# COEXPIX_schematics.net
KiCad netlist of a schematic drawn in Altium Designer
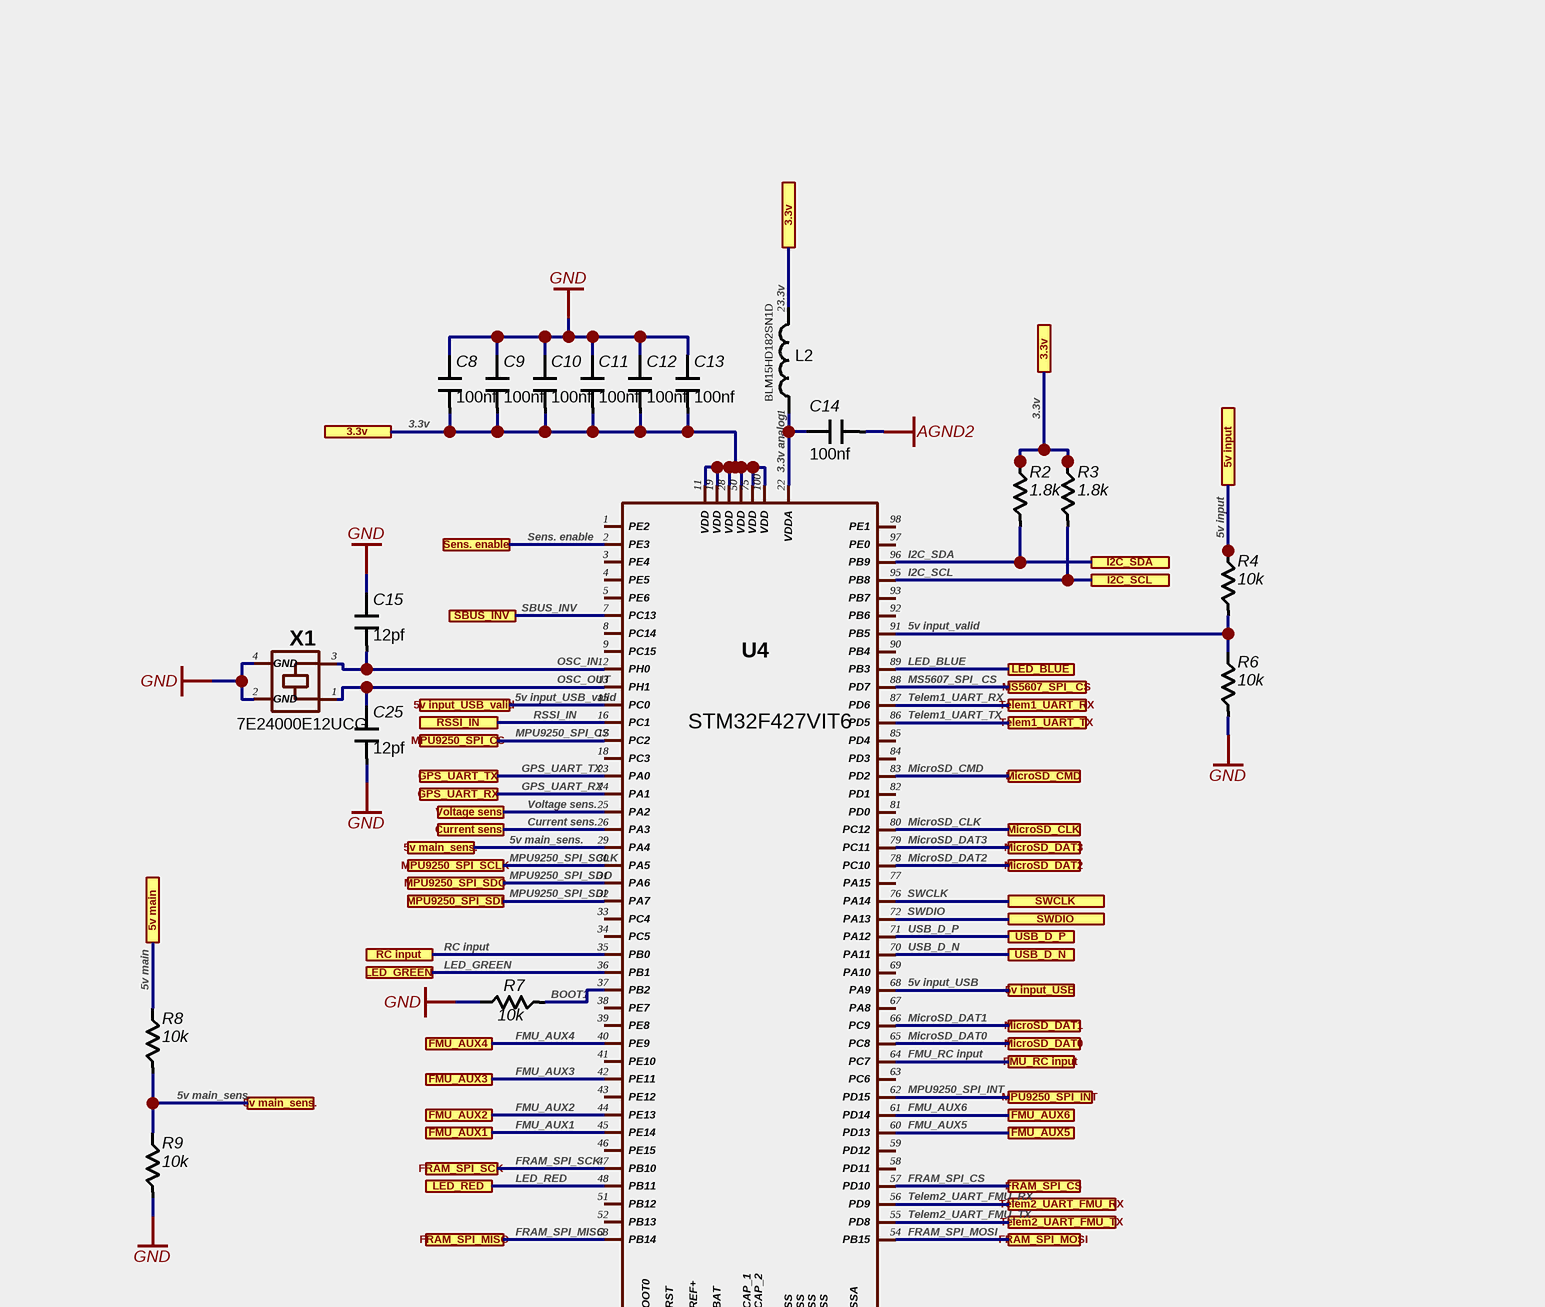
[diagram p0: COEXPIX schematics.SchDoc, top left]
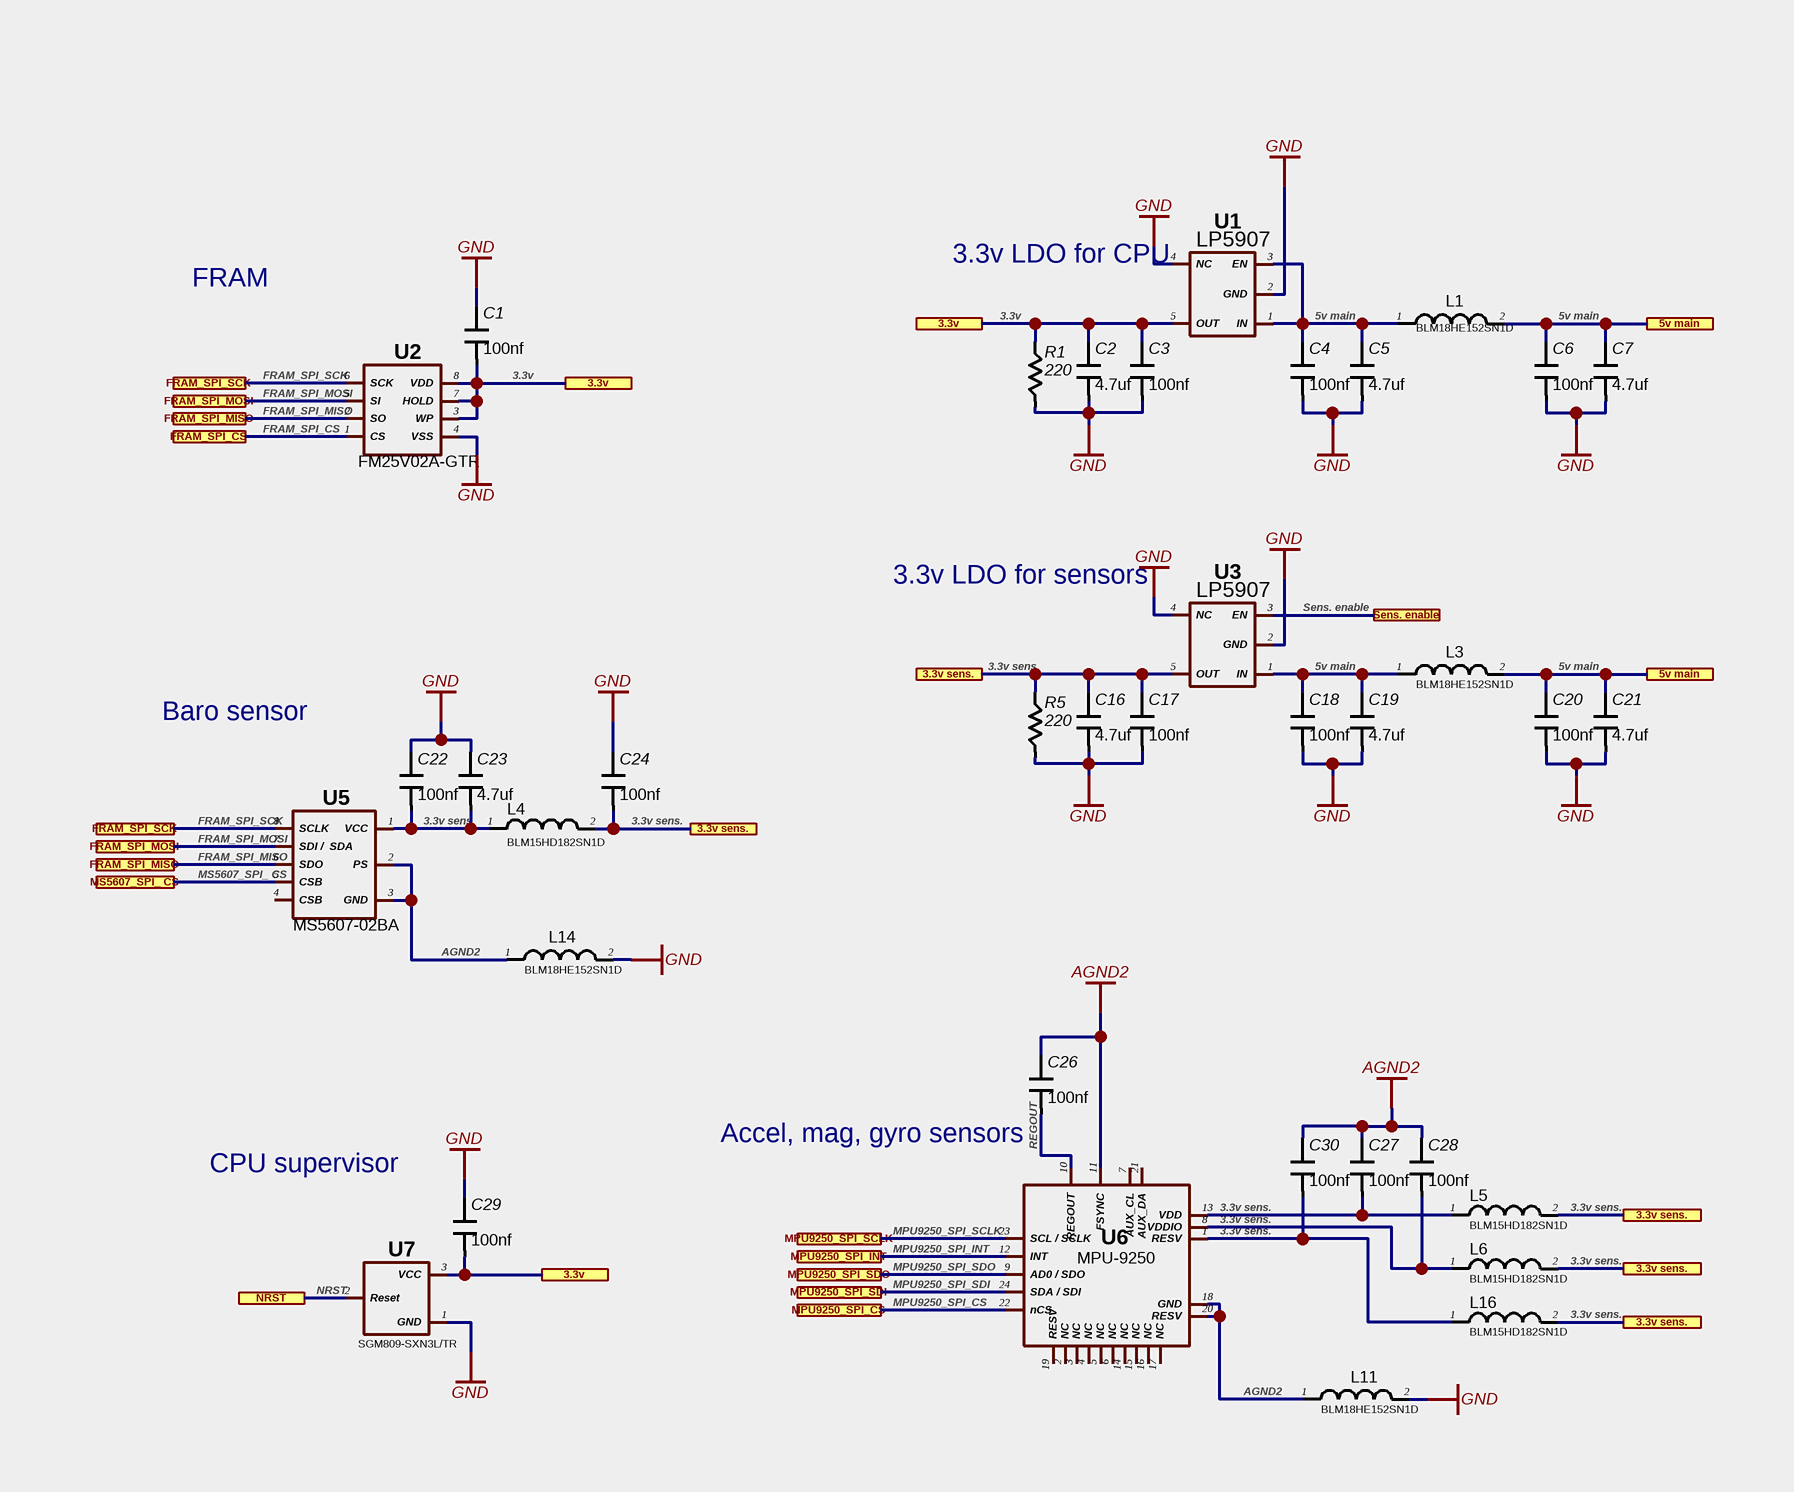
[diagram p1: COEXPIX schematics.SchDoc, top right]
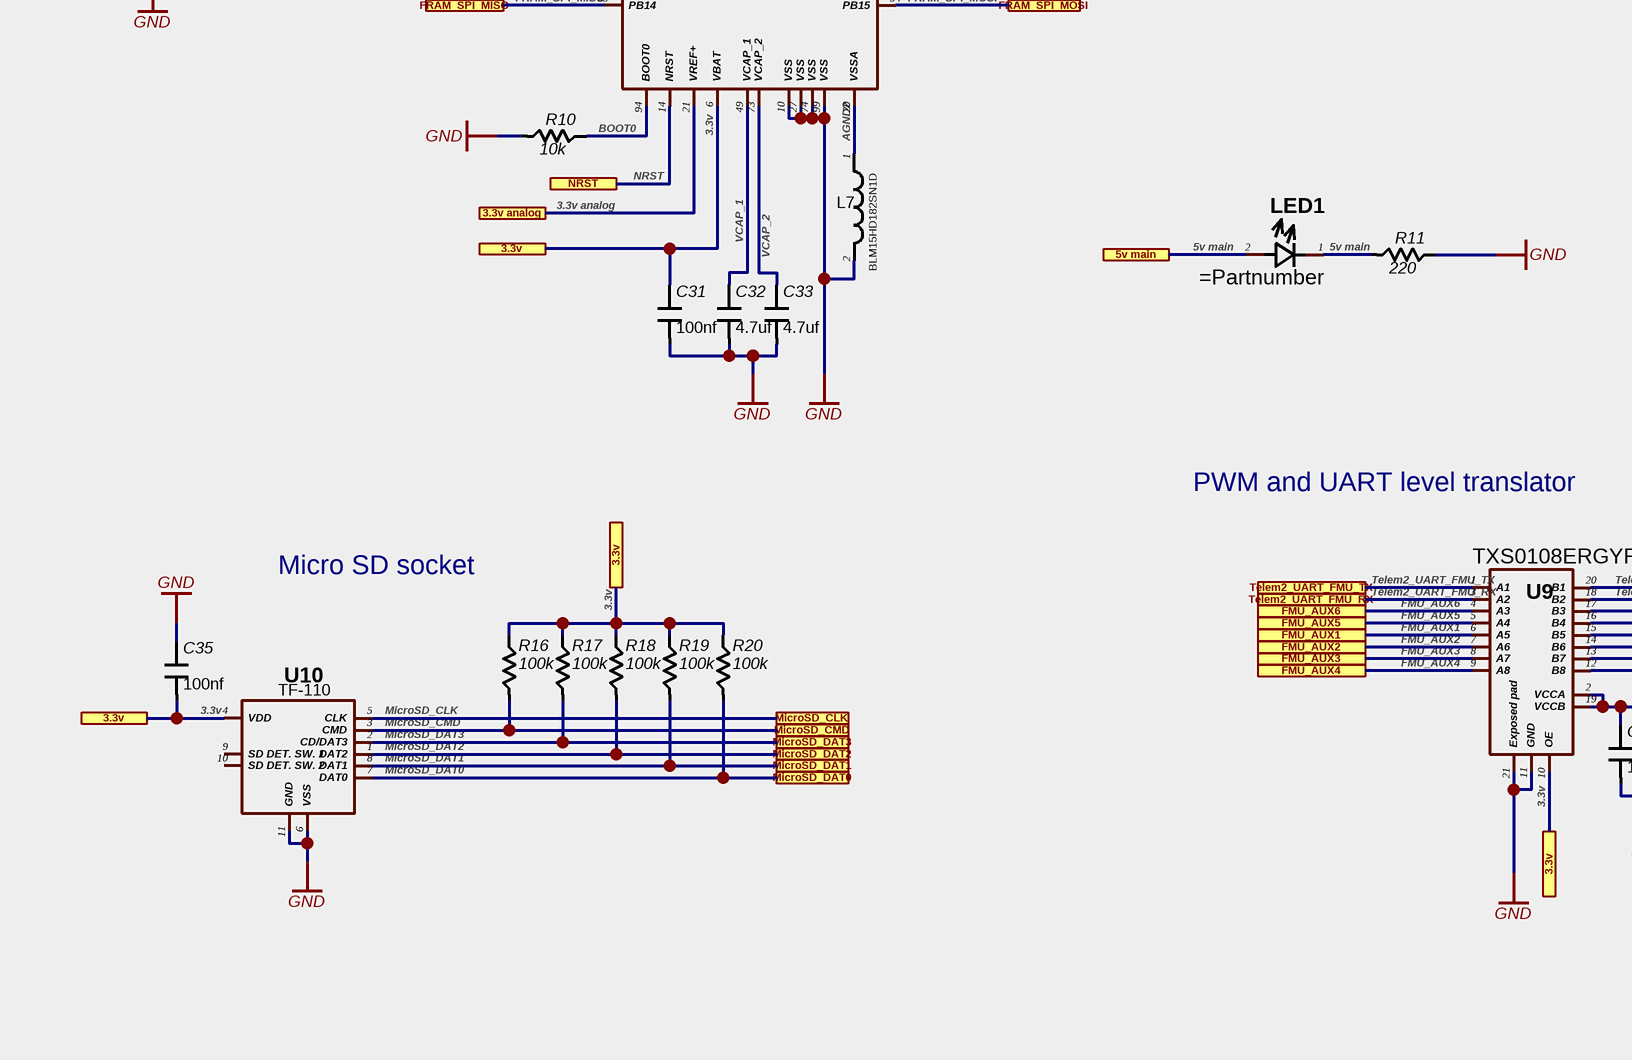
[diagram p2: COEXPIX schematics.SchDoc, bottom left]
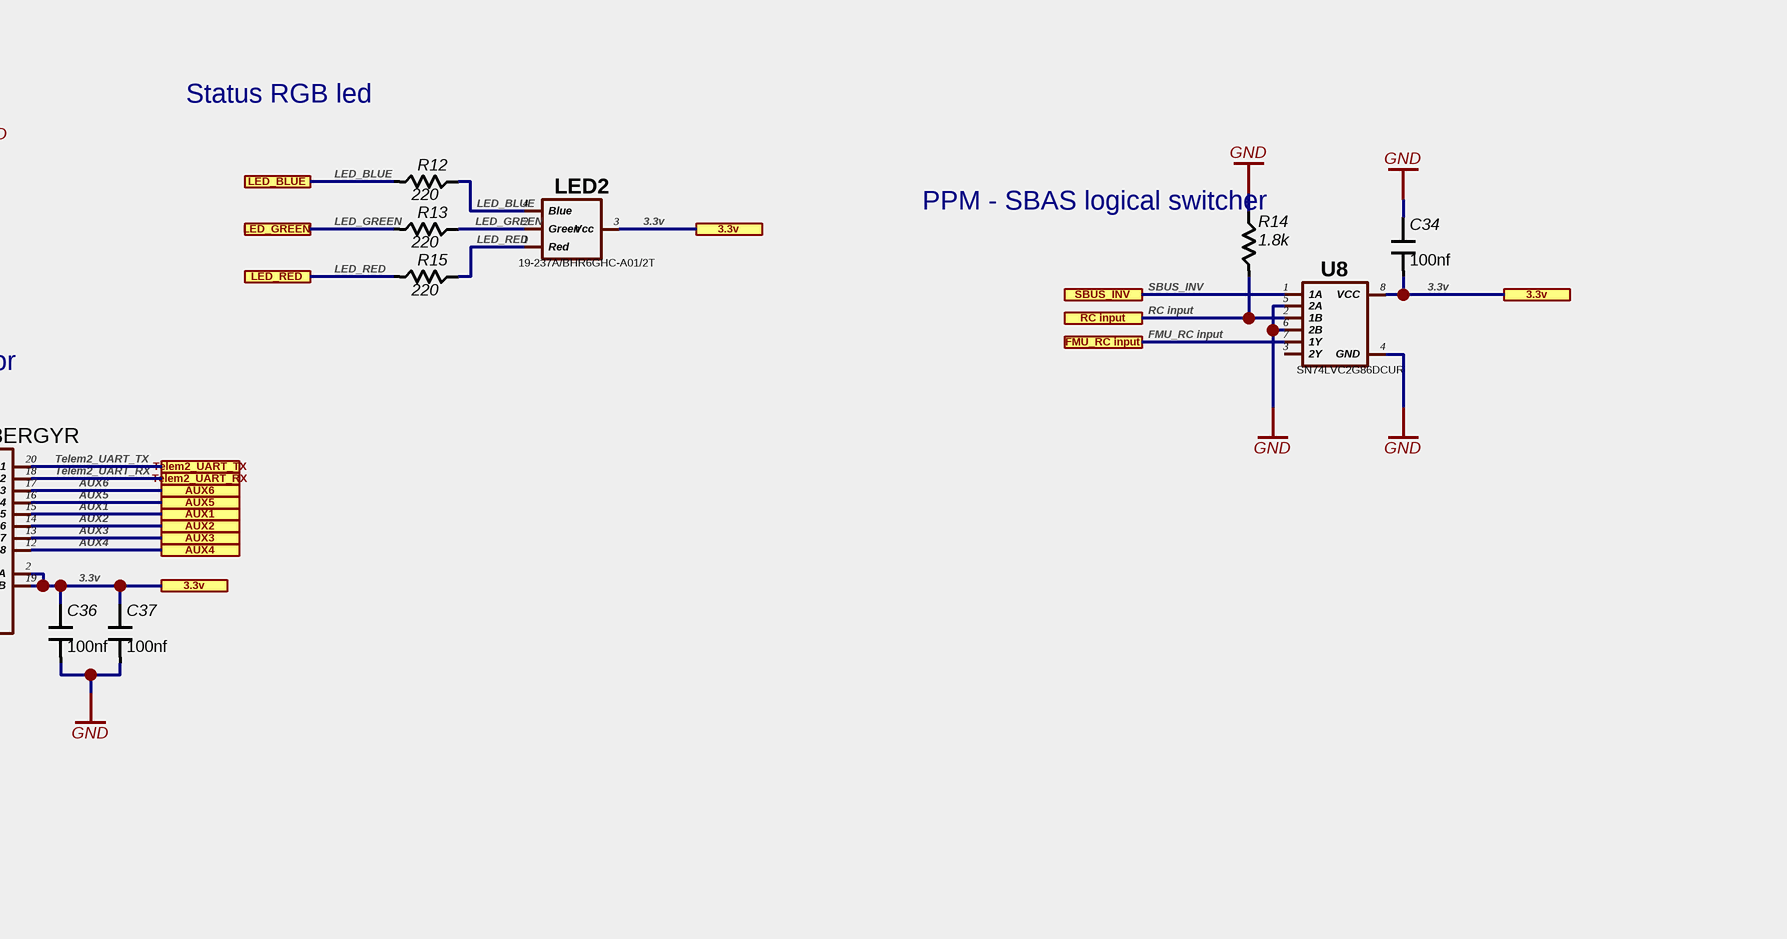
[diagram p3: COEXPIX schematics.SchDoc, bottom right]

(export (version "E")
  (design (tool "Eeschema 10.0.6"))
  (components
    (comp (ref "C1")
      (value "100nf")
      (footprint "Capasitor 0402")
      (description "Multilayer Ceramic Capacitors MLCC - SMD/SMT 100nF 16V 0402")
      (fields (field (name "PART NUMBER") "CC0402KRX7R7BB104") (field (name "MANUFACTURER") "YAGEO"))
      (libsource (lib "Schematic symbols library") (part "Capacitor MLCC"))
    )
    (comp (ref "C2")
      (value "4.7uf")
      (footprint "Capasitor 0402")
      (description "4.7uF ±20% 6.3V X5R 0402 Multilayer Ceramic Capacitor")
      (fields (field (name "PART NUMBER") "JMK105BBJ475MV-F") (field (name "MANUFACTURER") "Taiyo Yuden"))
      (libsource (lib "Schematic symbols library") (part "Capacitor MLCC"))
    )
    (comp (ref "C3")
      (value "100nf")
      (footprint "Capasitor 0402")
      (description "Multilayer Ceramic Capacitors MLCC - SMD/SMT 100nF 16V 0402")
      (fields (field (name "PART NUMBER") "CC0402KRX7R7BB104") (field (name "MANUFACTURER") "YAGEO"))
      (libsource (lib "Schematic symbols library") (part "Capacitor MLCC"))
    )
    (comp (ref "C4")
      (value "100nf")
      (footprint "Capasitor 0402")
      (description "Multilayer Ceramic Capacitors MLCC - SMD/SMT 100nF 16V 0402")
      (fields (field (name "PART NUMBER") "CC0402KRX7R7BB104") (field (name "MANUFACTURER") "YAGEO"))
      (libsource (lib "Schematic symbols library") (part "Capacitor MLCC"))
    )
    (comp (ref "C5")
      (value "4.7uf")
      (footprint "Capasitor 0402")
      (description "4.7uF ±20% 6.3V X5R 0402 Multilayer Ceramic Capacitor")
      (fields (field (name "PART NUMBER") "JMK105BBJ475MV-F") (field (name "MANUFACTURER") "Taiyo Yuden"))
      (libsource (lib "") (part "Capacitor MLCC_1"))
    )
    (comp (ref "C6")
      (value "100nf")
      (footprint "Capasitor 0402")
      (description "Multilayer Ceramic Capacitors MLCC - SMD/SMT 100nF 16V 0402")
      (fields (field (name "PART NUMBER") "CC0402KRX7R7BB104") (field (name "MANUFACTURER") "YAGEO"))
      (libsource (lib "Schematic symbols library") (part "Capacitor MLCC"))
    )
    (comp (ref "C7")
      (value "4.7uf")
      (footprint "Capasitor 0402")
      (description "4.7uF ±20% 6.3V X5R 0402 Multilayer Ceramic Capacitor")
      (fields (field (name "PART NUMBER") "JMK105BBJ475MV-F") (field (name "MANUFACTURER") "Taiyo Yuden"))
      (libsource (lib "Schematic symbols library") (part "Capacitor MLCC"))
    )
    (comp (ref "C8")
      (value "100nf")
      (footprint "Capasitor 0402")
      (description "Multilayer Ceramic Capacitors MLCC - SMD/SMT 100nF 16V 0402")
      (fields (field (name "PART NUMBER") "CC0402KRX7R7BB104") (field (name "MANUFACTURER") "YAGEO"))
      (libsource (lib "Schematic symbols library") (part "Capacitor MLCC"))
    )
    (comp (ref "C9")
      (value "100nf")
      (footprint "Capasitor 0402")
      (description "Multilayer Ceramic Capacitors MLCC - SMD/SMT 100nF 16V 0402")
      (fields (field (name "PART NUMBER") "CC0402KRX7R7BB104") (field (name "MANUFACTURER") "YAGEO"))
      (libsource (lib "Schematic symbols library") (part "Capacitor MLCC"))
    )
    (comp (ref "C10")
      (value "100nf")
      (footprint "Capasitor 0402")
      (description "Multilayer Ceramic Capacitors MLCC - SMD/SMT 100nF 16V 0402")
      (fields (field (name "PART NUMBER") "CC0402KRX7R7BB104") (field (name "MANUFACTURER") "YAGEO"))
      (libsource (lib "Schematic symbols library") (part "Capacitor MLCC"))
    )
    (comp (ref "C11")
      (value "100nf")
      (footprint "Capasitor 0402")
      (description "Multilayer Ceramic Capacitors MLCC - SMD/SMT 100nF 16V 0402")
      (fields (field (name "PART NUMBER") "CC0402KRX7R7BB104") (field (name "MANUFACTURER") "YAGEO"))
      (libsource (lib "Schematic symbols library") (part "Capacitor MLCC"))
    )
    (comp (ref "C12")
      (value "100nf")
      (footprint "Capasitor 0402")
      (description "Multilayer Ceramic Capacitors MLCC - SMD/SMT 100nF 16V 0402")
      (fields (field (name "PART NUMBER") "CC0402KRX7R7BB104") (field (name "MANUFACTURER") "YAGEO"))
      (libsource (lib "Schematic symbols library") (part "Capacitor MLCC"))
    )
    (comp (ref "C13")
      (value "100nf")
      (footprint "Capasitor 0402")
      (description "Multilayer Ceramic Capacitors MLCC - SMD/SMT 100nF 16V 0402")
      (fields (field (name "PART NUMBER") "CC0402KRX7R7BB104") (field (name "MANUFACTURER") "YAGEO"))
      (libsource (lib "Schematic symbols library") (part "Capacitor MLCC"))
    )
    (comp (ref "C14")
      (value "100nf")
      (footprint "Capasitor 0402")
      (description "Multilayer Ceramic Capacitors MLCC - SMD/SMT 100nF 16V 0402")
      (fields (field (name "PART NUMBER") "CC0402KRX7R7BB104") (field (name "MANUFACTURER") "YAGEO"))
      (libsource (lib "Schematic symbols library") (part "Capacitor MLCC"))
    )
    (comp (ref "C15")
      (value "12pf")
      (footprint "Capasitor 0402")
      (description "Multilayer Ceramic Capacitors MLCC - SMD/SMT 12pF 50V 0402")
      (fields (field (name "PART NUMBER") "CC0402JRNPO9BN120") (field (name "MANUFACTURER") "YAGEO"))
      (libsource (lib "Schematic symbols library") (part "Capacitor MLCC"))
    )
    (comp (ref "C16")
      (value "4.7uf")
      (footprint "Capasitor 0402")
      (description "4.7uF ±20% 6.3V X5R 0402 Multilayer Ceramic Capacitor")
      (fields (field (name "PART NUMBER") "JMK105BBJ475MV-F") (field (name "MANUFACTURER") "Taiyo Yuden"))
      (libsource (lib "Schematic symbols library") (part "Capacitor MLCC"))
    )
    (comp (ref "C17")
      (value "100nf")
      (footprint "Capasitor 0402")
      (description "Multilayer Ceramic Capacitors MLCC - SMD/SMT 100nF 16V 0402")
      (fields (field (name "PART NUMBER") "CC0402KRX7R7BB104") (field (name "MANUFACTURER") "YAGEO"))
      (libsource (lib "Schematic symbols library") (part "Capacitor MLCC"))
    )
    (comp (ref "C18")
      (value "100nf")
      (footprint "Capasitor 0402")
      (description "Multilayer Ceramic Capacitors MLCC - SMD/SMT 100nF 16V 0402")
      (fields (field (name "PART NUMBER") "CC0402KRX7R7BB104") (field (name "MANUFACTURER") "YAGEO"))
      (libsource (lib "Schematic symbols library") (part "Capacitor MLCC"))
    )
    (comp (ref "C19")
      (value "4.7uf")
      (footprint "Capasitor 0402")
      (description "4.7uF ±20% 6.3V X5R 0402 Multilayer Ceramic Capacitor")
      (fields (field (name "PART NUMBER") "JMK105BBJ475MV-F") (field (name "MANUFACTURER") "Taiyo Yuden"))
      (libsource (lib "") (part "Capacitor MLCC_1"))
    )
    (comp (ref "C20")
      (value "100nf")
      (footprint "Capasitor 0402")
      (description "Multilayer Ceramic Capacitors MLCC - SMD/SMT 100nF 16V 0402")
      (fields (field (name "PART NUMBER") "CC0402KRX7R7BB104") (field (name "MANUFACTURER") "YAGEO"))
      (libsource (lib "Schematic symbols library") (part "Capacitor MLCC"))
    )
    (comp (ref "C21")
      (value "4.7uf")
      (footprint "Capasitor 0402")
      (description "4.7uF ±20% 6.3V X5R 0402 Multilayer Ceramic Capacitor")
      (fields (field (name "PART NUMBER") "JMK105BBJ475MV-F") (field (name "MANUFACTURER") "Taiyo Yuden"))
      (libsource (lib "Schematic symbols library") (part "Capacitor MLCC"))
    )
    (comp (ref "C22")
      (value "100nf")
      (footprint "Capasitor 0402")
      (description "Multilayer Ceramic Capacitors MLCC - SMD/SMT 100nF 16V 0402")
      (fields (field (name "PART NUMBER") "CC0402KRX7R7BB104") (field (name "MANUFACTURER") "YAGEO"))
      (libsource (lib "Schematic symbols library") (part "Capacitor MLCC"))
    )
    (comp (ref "C23")
      (value "4.7uf")
      (footprint "Capasitor 0402")
      (description "4.7uF ±20% 6.3V X5R 0402 Multilayer Ceramic Capacitor")
      (fields (field (name "PART NUMBER") "JMK105BBJ475MV-F") (field (name "MANUFACTURER") "Taiyo Yuden"))
      (libsource (lib "Schematic symbols library") (part "Capacitor MLCC"))
    )
    (comp (ref "C24")
      (value "100nf")
      (footprint "Capasitor 0402")
      (description "Multilayer Ceramic Capacitors MLCC - SMD/SMT 100nF 16V 0402")
      (fields (field (name "PART NUMBER") "CC0402KRX7R7BB104") (field (name "MANUFACTURER") "YAGEO"))
      (libsource (lib "Schematic symbols library") (part "Capacitor MLCC"))
    )
    (comp (ref "C25")
      (value "12pf")
      (footprint "Capasitor 0402")
      (description "Multilayer Ceramic Capacitors MLCC - SMD/SMT 12pF 50V 0402")
      (fields (field (name "PART NUMBER") "CC0402JRNPO9BN120") (field (name "MANUFACTURER") "YAGEO"))
      (libsource (lib "Schematic symbols library") (part "Capacitor MLCC"))
    )
    (comp (ref "C26")
      (value "100nf")
      (footprint "Capasitor 0402")
      (description "Multilayer Ceramic Capacitors MLCC - SMD/SMT 100nF 16V 0402")
      (fields (field (name "PART NUMBER") "CC0402KRX7R7BB104") (field (name "MANUFACTURER") "YAGEO"))
      (libsource (lib "Schematic symbols library") (part "Capacitor MLCC"))
    )
    (comp (ref "C27")
      (value "100nf")
      (footprint "Capasitor 0402")
      (description "Multilayer Ceramic Capacitors MLCC - SMD/SMT 100nF 16V 0402")
      (fields (field (name "PART NUMBER") "CC0402KRX7R7BB104") (field (name "MANUFACTURER") "YAGEO"))
      (libsource (lib "") (part "Capacitor MLCC_1"))
    )
    (comp (ref "C28")
      (value "100nf")
      (footprint "Capasitor 0402")
      (description "Multilayer Ceramic Capacitors MLCC - SMD/SMT 100nF 16V 0402")
      (fields (field (name "PART NUMBER") "CC0402KRX7R7BB104") (field (name "MANUFACTURER") "YAGEO"))
      (libsource (lib "Schematic symbols library") (part "Capacitor MLCC"))
    )
    (comp (ref "C29")
      (value "100nf")
      (footprint "Capasitor 0402")
      (description "Multilayer Ceramic Capacitors MLCC - SMD/SMT 100nF 16V 0402")
      (fields (field (name "PART NUMBER") "CC0402KRX7R7BB104") (field (name "MANUFACTURER") "YAGEO"))
      (libsource (lib "Schematic symbols library") (part "Capacitor MLCC"))
    )
    (comp (ref "C30")
      (value "100nf")
      (footprint "Capasitor 0402")
      (description "Multilayer Ceramic Capacitors MLCC - SMD/SMT 100nF 16V 0402")
      (fields (field (name "PART NUMBER") "CC0402KRX7R7BB104") (field (name "MANUFACTURER") "YAGEO"))
      (libsource (lib "Schematic symbols library") (part "Capacitor MLCC"))
    )
    (comp (ref "C31")
      (value "100nf")
      (footprint "Capasitor 0402")
      (description "Multilayer Ceramic Capacitors MLCC - SMD/SMT 100nF 16V 0402")
      (fields (field (name "PART NUMBER") "CC0402KRX7R7BB104") (field (name "MANUFACTURER") "YAGEO"))
      (libsource (lib "Schematic symbols library") (part "Capacitor MLCC"))
    )
    (comp (ref "C32")
      (value "4.7uf")
      (footprint "Capasitor 0402")
      (description "4.7uF ±20% 6.3V X5R 0402 Multilayer Ceramic Capacitor")
      (fields (field (name "PART NUMBER") "JMK105BBJ475MV-F") (field (name "MANUFACTURER") "Taiyo Yuden"))
      (libsource (lib "Schematic symbols library") (part "Capacitor MLCC"))
    )
    (comp (ref "C33")
      (value "4.7uf")
      (footprint "Capasitor 0402")
      (description "4.7uF ±20% 6.3V X5R 0402 Multilayer Ceramic Capacitor")
      (fields (field (name "PART NUMBER") "JMK105BBJ475MV-F") (field (name "MANUFACTURER") "Taiyo Yuden"))
      (libsource (lib "Schematic symbols library") (part "Capacitor MLCC"))
    )
    (comp (ref "C34")
      (value "100nf")
      (footprint "Capasitor 0402")
      (description "Multilayer Ceramic Capacitors MLCC - SMD/SMT 100nF 16V 0402")
      (fields (field (name "PART NUMBER") "CC0402KRX7R7BB104") (field (name "MANUFACTURER") "YAGEO"))
      (libsource (lib "Schematic symbols library") (part "Capacitor MLCC"))
    )
    (comp (ref "C35")
      (value "100nf")
      (footprint "Capasitor 0402")
      (description "Multilayer Ceramic Capacitors MLCC - SMD/SMT 100nF 16V 0402")
      (fields (field (name "PART NUMBER") "CC0402KRX7R7BB104") (field (name "MANUFACTURER") "YAGEO"))
      (libsource (lib "Schematic symbols library") (part "Capacitor MLCC"))
    )
    (comp (ref "C36")
      (value "100nf")
      (footprint "Capasitor 0402")
      (description "Multilayer Ceramic Capacitors MLCC - SMD/SMT 100nF 16V 0402")
      (fields (field (name "PART NUMBER") "CC0402KRX7R7BB104") (field (name "MANUFACTURER") "YAGEO"))
      (libsource (lib "Schematic symbols library") (part "Capacitor MLCC"))
    )
    (comp (ref "C37")
      (value "100nf")
      (footprint "Capasitor 0402")
      (description "Multilayer Ceramic Capacitors MLCC - SMD/SMT 100nF 16V 0402")
      (fields (field (name "PART NUMBER") "CC0402KRX7R7BB104") (field (name "MANUFACTURER") "YAGEO"))
      (libsource (lib "Schematic symbols library") (part "Capacitor MLCC"))
    )
    (comp (ref "L1")
      (value "BLM18HE152SN1D")
      (footprint "Ferrite bead 0603")
      (description "Beads 0603")
      (fields (field (name "MANUFACTURER") "Murata"))
      (libsource (lib "Schematic symbols library") (part "FB / Inductor"))
    )
    (comp (ref "L2")
      (value "BLM15HD182SN1D")
      (footprint "Ferrite bead 0402")
      (description "1.8kΩ @ 100MHz 200mA 1 2.2Ω 0402 Ferrite Bead")
      (fields (field (name "MANUFACTURER") "Murata Electronics"))
      (libsource (lib "Schematic symbols library") (part "FB / Inductor"))
    )
    (comp (ref "L3")
      (value "BLM18HE152SN1D")
      (footprint "Ferrite bead 0603")
      (description "Beads 0603")
      (fields (field (name "MANUFACTURER") "Murata"))
      (libsource (lib "Schematic symbols library") (part "FB / Inductor"))
    )
    (comp (ref "L4")
      (value "BLM15HD182SN1D")
      (footprint "Ferrite bead 0402")
      (description "1.8kΩ @ 100MHz 200mA 1 2.2Ω 0402 Ferrite Bead")
      (fields (field (name "MANUFACTURER") "Murata Electronics"))
      (libsource (lib "Schematic symbols library") (part "FB / Inductor"))
    )
    (comp (ref "L5")
      (value "BLM15HD182SN1D")
      (footprint "Ferrite bead 0402")
      (description "1.8kΩ @ 100MHz 200mA 1 2.2Ω 0402 Ferrite Bead")
      (fields (field (name "MANUFACTURER") "Murata Electronics"))
      (libsource (lib "Schematic symbols library") (part "FB / Inductor"))
    )
    (comp (ref "L6")
      (value "BLM15HD182SN1D")
      (footprint "Ferrite bead 0402")
      (description "1.8kΩ @ 100MHz 200mA 1 2.2Ω 0402 Ferrite Bead")
      (fields (field (name "MANUFACTURER") "Murata Electronics"))
      (libsource (lib "Schematic symbols library") (part "FB / Inductor"))
    )
    (comp (ref "L7")
      (value "BLM15HD182SN1D")
      (footprint "Ferrite bead 0402")
      (description "1.8kΩ @ 100MHz 200mA 1 2.2Ω 0402 Ferrite Bead")
      (fields (field (name "MANUFACTURER") "Murata Electronics"))
      (libsource (lib "Schematic symbols library") (part "FB / Inductor"))
    )
    (comp (ref "L11")
      (value "BLM18HE152SN1D")
      (footprint "Ferrite bead 0603")
      (description "Beads 0603")
      (fields (field (name "MANUFACTURER") "Murata"))
      (libsource (lib "Schematic symbols library") (part "FB / Inductor"))
    )
    (comp (ref "L14")
      (value "BLM18HE152SN1D")
      (footprint "Ferrite bead 0603")
      (description "Beads 0603")
      (fields (field (name "MANUFACTURER") "Murata"))
      (libsource (lib "Schematic symbols library") (part "FB / Inductor"))
    )
    (comp (ref "L16")
      (value "BLM15HD182SN1D")
      (footprint "Ferrite bead 0402")
      (description "1.8kΩ @ 100MHz 200mA 1 2.2Ω 0402 Ferrite Bead")
      (fields (field (name "MANUFACTURER") "Murata Electronics"))
      (libsource (lib "Schematic symbols library") (part "FB / Inductor"))
    )
    (comp (ref "LED1")
      (value "~")
      (footprint "Led 0603")
      (description "Green 520~535nm 0603 Light Emitting Diode")
      (fields
        (field (name "PART NUMBER") "19-217/GHC-YR1S2/3T")
        (field (name "MANUFACTURER") "Everlight Elec")
      )
      (libsource (lib "Schematic symbols library") (part "LED"))
    )
    (comp (ref "LED2")
      (value "19-237A/BHR6GHC-A01/2T")
      (footprint "Everlight RGB LED")
      (description "RGB614~628nmRed,518~528nmGreen,465~475nmBlue SMD,1.6x1.6mm Light Emitting Diode")
      (fields (field (name "MANUFACTURER") "Everlight Elec"))
      (libsource (lib "Schematic symbols library") (part "Everlight 19-237A"))
    )
    (comp (ref "R1")
      (value "220")
      (footprint "Resistor 0402")
      (description "Chip Resistor - Surface Mount 220Ohms ±1% 1/16W 0402")
      (fields (field (name "PART NUMBER") "0402WGF2200TCE") (field (name "MANUFACTURER") "Uniroyal Elec"))
      (libsource (lib "Schematic symbols library") (part "Resistor"))
    )
    (comp (ref "R2")
      (value "1.8k")
      (footprint "Resistor 0402")
      (description "Chip Resistor - Surface Mount 1.8KOhms ±1% 1/16W 0402")
      (fields (field (name "PART NUMBER") "0402WGF1801TCE") (field (name "MANUFACTURER") "Uniroyal Elec"))
      (libsource (lib "Schematic symbols library") (part "Resistor"))
    )
    (comp (ref "R3")
      (value "1.8k")
      (footprint "Resistor 0402")
      (description "Chip Resistor - Surface Mount 1.8KOhms ±1% 1/16W 0402")
      (fields (field (name "PART NUMBER") "0402WGF1801TCE") (field (name "MANUFACTURER") "Uniroyal Elec"))
      (libsource (lib "Schematic symbols library") (part "Resistor"))
    )
    (comp (ref "R4")
      (value "10k")
      (footprint "Resistor 0402")
      (description "Chip Resistor - Surface Mount 10KOhms ±1% 1/16W 0402")
      (fields (field (name "PART NUMBER") "RC0402FR-0710KL") (field (name "MANUFACTURER") "YAGEO"))
      (libsource (lib "Schematic symbols library") (part "Resistor"))
    )
    (comp (ref "R5")
      (value "220")
      (footprint "Resistor 0402")
      (description "Chip Resistor - Surface Mount 220Ohms ±1% 1/16W 0402")
      (fields (field (name "PART NUMBER") "0402WGF2200TCE") (field (name "MANUFACTURER") "Uniroyal Elec"))
      (libsource (lib "Schematic symbols library") (part "Resistor"))
    )
    (comp (ref "R6")
      (value "10k")
      (footprint "Resistor 0402")
      (description "Chip Resistor - Surface Mount 10KOhms ±1% 1/16W 0402")
      (fields (field (name "PART NUMBER") "RC0402FR-0710KL") (field (name "MANUFACTURER") "YAGEO"))
      (libsource (lib "Schematic symbols library") (part "Resistor"))
    )
    (comp (ref "R7")
      (value "10k")
      (footprint "Resistor 0402")
      (description "Chip Resistor - Surface Mount 10KOhms ±1% 1/16W 0402")
      (fields (field (name "PART NUMBER") "RC0402FR-0710KL") (field (name "MANUFACTURER") "YAGEO"))
      (libsource (lib "Schematic symbols library") (part "Resistor"))
    )
    (comp (ref "R8")
      (value "10k")
      (footprint "Resistor 0402")
      (description "Chip Resistor - Surface Mount 10KOhms ±1% 1/16W 0402")
      (fields (field (name "PART NUMBER") "RC0402FR-0710KL") (field (name "MANUFACTURER") "YAGEO"))
      (libsource (lib "Schematic symbols library") (part "Resistor"))
    )
    (comp (ref "R9")
      (value "10k")
      (footprint "Resistor 0402")
      (description "Chip Resistor - Surface Mount 10KOhms ±1% 1/16W 0402")
      (fields (field (name "PART NUMBER") "RC0402FR-0710KL") (field (name "MANUFACTURER") "YAGEO"))
      (libsource (lib "Schematic symbols library") (part "Resistor"))
    )
    (comp (ref "R10")
      (value "10k")
      (footprint "Resistor 0402")
      (description "Chip Resistor - Surface Mount 10KOhms ±1% 1/16W 0402")
      (fields (field (name "PART NUMBER") "RC0402FR-0710KL") (field (name "MANUFACTURER") "YAGEO"))
      (libsource (lib "Schematic symbols library") (part "Resistor"))
    )
    (comp (ref "R11")
      (value "220")
      (footprint "Resistor 0402")
      (description "Chip Resistor - Surface Mount 220Ohms ±1% 1/16W 0402")
      (fields (field (name "PART NUMBER") "0402WGF2200TCE") (field (name "MANUFACTURER") "Uniroyal Elec"))
      (libsource (lib "Schematic symbols library") (part "Resistor"))
    )
    (comp (ref "R12")
      (value "220")
      (footprint "Resistor 0402")
      (description "Chip Resistor - Surface Mount 220Ohms ±1% 1/16W 0402")
      (fields (field (name "PART NUMBER") "0402WGF2200TCE") (field (name "MANUFACTURER") "Uniroyal Elec"))
      (libsource (lib "Schematic symbols library") (part "Resistor"))
    )
    (comp (ref "R13")
      (value "220")
      (footprint "Resistor 0402")
      (description "Chip Resistor - Surface Mount 220Ohms ±1% 1/16W 0402")
      (fields (field (name "PART NUMBER") "0402WGF2200TCE") (field (name "MANUFACTURER") "Uniroyal Elec"))
      (libsource (lib "Schematic symbols library") (part "Resistor"))
    )
    (comp (ref "R14")
      (value "1.8k")
      (footprint "Resistor 0402")
      (description "Chip Resistor - Surface Mount 1.8KOhms ±1% 1/16W 0402")
      (fields (field (name "PART NUMBER") "0402WGF1801TCE") (field (name "MANUFACTURER") "Uniroyal Elec"))
      (libsource (lib "Schematic symbols library") (part "Resistor"))
    )
    (comp (ref "R15")
      (value "220")
      (footprint "Resistor 0402")
      (description "Chip Resistor - Surface Mount 220Ohms ±1% 1/16W 0402")
      (fields (field (name "PART NUMBER") "0402WGF2200TCE") (field (name "MANUFACTURER") "Uniroyal Elec"))
      (libsource (lib "Schematic symbols library") (part "Resistor"))
    )
    (comp (ref "R16")
      (value "100k")
      (footprint "Resistor 0402")
      (description "Chip Resistor - Surface Mount 100KOhms ±1% 1/16W 0402")
      (fields (field (name "PART NUMBER") "RC0402FR-07100KL") (field (name "MANUFACTURER") "YAGEO"))
      (libsource (lib "Schematic symbols library") (part "Resistor"))
    )
    (comp (ref "R17")
      (value "100k")
      (footprint "Resistor 0402")
      (description "Chip Resistor - Surface Mount 100KOhms ±1% 1/16W 0402")
      (fields (field (name "PART NUMBER") "RC0402FR-07100KL") (field (name "MANUFACTURER") "YAGEO"))
      (libsource (lib "Schematic symbols library") (part "Resistor"))
    )
    (comp (ref "R18")
      (value "100k")
      (footprint "Resistor 0402")
      (description "Chip Resistor - Surface Mount 100KOhms ±1% 1/16W 0402")
      (fields (field (name "PART NUMBER") "RC0402FR-07100KL") (field (name "MANUFACTURER") "YAGEO"))
      (libsource (lib "Schematic symbols library") (part "Resistor"))
    )
    (comp (ref "R19")
      (value "100k")
      (footprint "Resistor 0402")
      (description "Chip Resistor - Surface Mount 100KOhms ±1% 1/16W 0402")
      (fields (field (name "PART NUMBER") "RC0402FR-07100KL") (field (name "MANUFACTURER") "YAGEO"))
      (libsource (lib "Schematic symbols library") (part "Resistor"))
    )
    (comp (ref "R20")
      (value "100k")
      (footprint "Resistor 0402")
      (description "Chip Resistor - Surface Mount 100KOhms ±1% 1/16W 0402")
      (fields (field (name "PART NUMBER") "RC0402FR-07100KL") (field (name "MANUFACTURER") "YAGEO"))
      (libsource (lib "Schematic symbols library") (part "Resistor"))
    )
    (comp (ref "U1")
      (value "LP5907")
      (footprint "SOT23-5")
      (description "Linear Voltage Regulators SOT-23-5")
      (fields (field (name "MANUFACTURER") "Texas Instruments"))
      (libsource (lib "Schematic symbols library") (part "LP5907"))
    )
    (comp (ref "U2")
      (value "FM25V02A-GTR")
      (footprint "SOIC-8")
      (description "FRAM FRAM 256Kb (32K x 8) SPI SOIC-8_150mil")
      (fields (field (name "MANUFACTURER") "Cypress Semicon"))
      (libsource (lib "Schematic symbols library") (part "FM25V02A"))
    )
    (comp (ref "U3")
      (value "LP5907")
      (footprint "SOT23-5")
      (description "Linear Voltage Regulators SOT-23-5")
      (fields (field (name "MANUFACTURER") "Texas Instruments"))
      (libsource (lib "Schematic symbols library") (part "LP5907"))
    )
    (comp (ref "U4")
      (value "STM32F427VIT6")
      (footprint "LQFP100 0.5")
      (description "ARM® Cortex®-M4 STM32F4 Microcontroller IC 32-Bit 180MHz 2MB (2M x 8) FLASH 100-LQFP (14x14)")
      (fields (field (name "MANUFACTURER") "STMicroelectronics"))
      (libsource (lib "Schematic symbols library") (part "STM32F427VIT6"))
    )
    (comp (ref "U5")
      (value "MS5607-02BA")
      (footprint "MS5611")
      (fields (field (name "MANUFACTURER") "meas-spec"))
      (libsource (lib "Schematic symbols library") (part "MS5607-02BA"))
    )
    (comp (ref "U6")
      (value "MPU-9250")
      (footprint "QFN24 3x3mm (0.4mm)")
      (description "IMU ACCEL/GYRO/MAG I2C/SPI 24QFN")
      (fields (field (name "MANUFACTURER") "TDK InvenSense"))
      (libsource (lib "Schematic symbols library") (part "mpu9250"))
    )
    (comp (ref "U7")
      (value "SGM809-SXN3L/TR")
      (footprint "SOT23-3 LP")
      (fields (field (name "MANUFACTURER") "SGMICRO"))
      (libsource (lib "Schematic symbols library") (part "SGM809-SXN3L/TR"))
    )
    (comp (ref "U8")
      (value "SN74LVC2G86DCUR")
      (footprint "VSSOP8 0.5mm")
      (description "74 Series SPST-NC 2 1.65V ~ 5.5V VSSOP-8_2x2.3x05P")
      (fields (field (name "MANUFACTURER") "Texas Instruments"))
      (libsource (lib "Schematic symbols library") (part "SN74LVC2G86DCUR"))
    )
    (comp (ref "U9")
      (value "TXS0108ERGYR")
      (footprint "VQFN20 4.50x3.50mm (0.5mm)")
      (description "Level Translators, Shifters VQFN-20")
      (fields (field (name "MANUFACTURER") "Texas Instruments"))
      (libsource (lib "Schematic symbols library") (part "TXS0108ERGYR"))
    )
    (comp (ref "U10")
      (value "TF-110")
      (footprint "MicroSD (2)")
      (description "microSD™ Memory Card 8 connector 11.25x11.35x1.32mm Card Sockets Connector")
      (fields (field (name "MANUFACTURER") "XUNPU"))
      (libsource (lib "Schematic symbols library") (part "MicroSD socket"))
    )
    (comp (ref "X1")
      (value "7E24000E12UCG")
      (footprint "SMD-2520_4P")
      (description "SMD Crystal Resonators 24MHz ±10ppm SMD-2520_4P")
      (fields (field (name "MANUFACTURER") "SHENZHEN CRYSTAL TECH"))
      (libsource (lib "Schematic symbols library") (part "Crystal oscillator"))
    )
  )
  (nets
    (net (code "1") (name "/3.3v") (class "Default")
      (node (ref "C1") (pin "2") (pinfunction "2_2") (pintype "passive"))
      (node (ref "C10") (pin "2") (pinfunction "2_2") (pintype "passive"))
      (node (ref "C11") (pin "2") (pinfunction "2_2") (pintype "passive"))
      (node (ref "C12") (pin "2") (pinfunction "2_2") (pintype "passive"))
      (node (ref "C13") (pin "2") (pinfunction "2_2") (pintype "passive"))
      (node (ref "C2") (pin "1") (pinfunction "1_1") (pintype "passive"))
      (node (ref "C29") (pin "2") (pinfunction "2_2") (pintype "passive"))
      (node (ref "C3") (pin "1") (pinfunction "1_1") (pintype "passive"))
      (node (ref "C31") (pin "1") (pinfunction "1_1") (pintype "passive"))
      (node (ref "C34") (pin "2") (pinfunction "2_2") (pintype "passive"))
      (node (ref "C35") (pin "2") (pinfunction "2_2") (pintype "passive"))
      (node (ref "C36") (pin "1") (pinfunction "1_1") (pintype "passive"))
      (node (ref "C37") (pin "1") (pinfunction "1_1") (pintype "passive"))
      (node (ref "C8") (pin "2") (pinfunction "2_2") (pintype "passive"))
      (node (ref "C9") (pin "2") (pinfunction "2_2") (pintype "passive"))
      (node (ref "L2") (pin "2") (pintype "power_in"))
      (node (ref "LED2") (pin "3") (pinfunction "Vcc_3") (pintype "power_in"))
      (node (ref "R1") (pin "1") (pinfunction "1_1") (pintype "passive"))
      (node (ref "R16") (pin "1") (pinfunction "1_1") (pintype "passive"))
      (node (ref "R17") (pin "1") (pinfunction "1_1") (pintype "passive"))
      (node (ref "R18") (pin "1") (pinfunction "1_1") (pintype "passive"))
      (node (ref "R19") (pin "1") (pinfunction "1_1") (pintype "passive"))
      (node (ref "R2") (pin "1") (pinfunction "1_1") (pintype "passive"))
      (node (ref "R20") (pin "1") (pinfunction "1_1") (pintype "passive"))
      (node (ref "R3") (pin "1") (pinfunction "1_1") (pintype "passive"))
      (node (ref "U1") (pin "5") (pinfunction "OUT_5") (pintype "power_in"))
      (node (ref "U10") (pin "4") (pinfunction "VDD_4") (pintype "power_in"))
      (node (ref "U2") (pin "3") (pinfunction "WP_3") (pintype "power_in"))
      (node (ref "U2") (pin "7") (pinfunction "HOLD_7") (pintype "power_in"))
      (node (ref "U2") (pin "8") (pinfunction "VDD_8") (pintype "power_in"))
      (node (ref "U4") (pin "100") (pinfunction "VDD_100") (pintype "power_in"))
      (node (ref "U4") (pin "11") (pinfunction "VDD_11") (pintype "power_in"))
      (node (ref "U4") (pin "19") (pinfunction "VDD_19") (pintype "power_in"))
      (node (ref "U4") (pin "28") (pinfunction "VDD_28") (pintype "power_in"))
      (node (ref "U4") (pin "50") (pinfunction "VDD_50") (pintype "power_in"))
      (node (ref "U4") (pin "6") (pinfunction "VBAT_6") (pintype "power_in"))
      (node (ref "U4") (pin "75") (pinfunction "VDD_75") (pintype "power_in"))
      (node (ref "U7") (pin "3") (pinfunction "VCC_3") (pintype "power_in"))
      (node (ref "U8") (pin "8") (pinfunction "VCC_8") (pintype "power_in"))
      (node (ref "U9") (pin "10") (pinfunction "OE_10") (pintype "power_in"))
      (node (ref "U9") (pin "19") (pinfunction "VCCB_19") (pintype "power_in"))
      (node (ref "U9") (pin "2") (pinfunction "VCCA_2") (pintype "power_in"))
    )
    (net (code "2") (name "/3.3v analog") (class "Default")
      (node (ref "C14") (pin "1") (pinfunction "1_1") (pintype "passive"))
      (node (ref "L2") (pin "1") (pintype "power_in"))
      (node (ref "U4") (pin "21") (pinfunction "VREF+_21") (pintype "power_in"))
      (node (ref "U4") (pin "22") (pinfunction "VDDA_22") (pintype "power_in"))
    )
    (net (code "3") (name "/3.3v sens.") (class "Default")
      (node (ref "C16") (pin "1") (pinfunction "1_1") (pintype "passive"))
      (node (ref "C17") (pin "1") (pinfunction "1_1") (pintype "passive"))
      (node (ref "C22") (pin "2") (pinfunction "2_2") (pintype "passive"))
      (node (ref "C23") (pin "2") (pinfunction "2_2") (pintype "passive"))
      (node (ref "C24") (pin "2") (pinfunction "2_2") (pintype "passive"))
      (node (ref "C27") (pin "2") (pinfunction "2_2") (pintype "passive"))
      (node (ref "C28") (pin "2") (pinfunction "2_2") (pintype "passive"))
      (node (ref "C30") (pin "2") (pinfunction "2_2") (pintype "passive"))
      (node (ref "L16") (pin "1") (pintype "power_in"))
      (node (ref "L16") (pin "2") (pintype "power_in"))
      (node (ref "L4") (pin "1") (pintype "power_in"))
      (node (ref "L4") (pin "2") (pintype "power_in"))
      (node (ref "L5") (pin "1") (pintype "power_in"))
      (node (ref "L5") (pin "2") (pintype "power_in"))
      (node (ref "L6") (pin "1") (pintype "power_in"))
      (node (ref "L6") (pin "2") (pintype "power_in"))
      (node (ref "R5") (pin "1") (pinfunction "1_1") (pintype "passive"))
      (node (ref "U3") (pin "5") (pinfunction "OUT_5") (pintype "power_in"))
      (node (ref "U5") (pin "1") (pinfunction "VCC_1") (pintype "power_in"))
      (node (ref "U6") (pin "1") (pinfunction "RESV_1") (pintype "power_in"))
      (node (ref "U6") (pin "13") (pinfunction "VDD_13") (pintype "power_in"))
      (node (ref "U6") (pin "8") (pinfunction "VDDIO_8") (pintype "power_in"))
    )
    (net (code "4") (name "/5v input") (class "Default")
      (node (ref "R4") (pin "1") (pinfunction "1_1") (pintype "passive"))
    )
    (net (code "5") (name "/5v input_USB") (class "Default")
      (node (ref "U4") (pin "68") (pinfunction "PA9_68") (pintype "power_in"))
    )
    (net (code "6") (name "/5v input_USB_valid") (class "Default")
      (node (ref "U4") (pin "15") (pinfunction "PC0_15") (pintype "power_in"))
    )
    (net (code "7") (name "/5v input_valid") (class "Default")
      (node (ref "R4") (pin "2") (pinfunction "2_2") (pintype "passive"))
      (node (ref "R6") (pin "1") (pinfunction "1_1") (pintype "passive"))
      (node (ref "U4") (pin "91") (pinfunction "PB5_91") (pintype "power_in"))
    )
    (net (code "8") (name "/5v main") (class "Default")
      (node (ref "C18") (pin "1") (pinfunction "1_1") (pintype "passive"))
      (node (ref "C19") (pin "1") (pinfunction "1_1") (pintype "passive"))
      (node (ref "C20") (pin "1") (pinfunction "1_1") (pintype "passive"))
      (node (ref "C21") (pin "1") (pinfunction "1_1") (pintype "passive"))
      (node (ref "C4") (pin "1") (pinfunction "1_1") (pintype "passive"))
      (node (ref "C5") (pin "1") (pinfunction "1_1") (pintype "passive"))
      (node (ref "C6") (pin "1") (pinfunction "1_1") (pintype "passive"))
      (node (ref "C7") (pin "1") (pinfunction "1_1") (pintype "passive"))
      (node (ref "L1") (pin "1") (pintype "power_in"))
      (node (ref "L1") (pin "2") (pintype "power_in"))
      (node (ref "L3") (pin "1") (pintype "power_in"))
      (node (ref "L3") (pin "2") (pintype "power_in"))
      (node (ref "LED1") (pin "1") (pintype "power_in"))
      (node (ref "LED1") (pin "2") (pintype "power_in"))
      (node (ref "R11") (pin "2") (pinfunction "2_2") (pintype "passive"))
      (node (ref "R8") (pin "1") (pinfunction "1_1") (pintype "passive"))
      (node (ref "U1") (pin "1") (pinfunction "IN_1") (pintype "power_in"))
      (node (ref "U1") (pin "3") (pinfunction "EN_3") (pintype "power_in"))
      (node (ref "U3") (pin "1") (pinfunction "IN_1") (pintype "power_in"))
    )
    (net (code "9") (name "/5v main_sens.") (class "Default")
      (node (ref "R8") (pin "2") (pinfunction "2_2") (pintype "passive"))
      (node (ref "R9") (pin "1") (pinfunction "1_1") (pintype "passive"))
      (node (ref "U4") (pin "29") (pinfunction "PA4_29") (pintype "power_in"))
    )
    (net (code "10") (name "/AUX1") (class "Default")
      (node (ref "U9") (pin "15") (pinfunction "B5_15") (pintype "power_in"))
    )
    (net (code "11") (name "/AUX2") (class "Default")
      (node (ref "U9") (pin "14") (pinfunction "B6_14") (pintype "power_in"))
    )
    (net (code "12") (name "/AUX3") (class "Default")
      (node (ref "U9") (pin "13") (pinfunction "B7_13") (pintype "power_in"))
    )
    (net (code "13") (name "/AUX4") (class "Default")
      (node (ref "U9") (pin "12") (pinfunction "B8_12") (pintype "power_in"))
    )
    (net (code "14") (name "/AUX5") (class "Default")
      (node (ref "U9") (pin "16") (pinfunction "B4_16") (pintype "power_in"))
    )
    (net (code "15") (name "/AUX6") (class "Default")
      (node (ref "U9") (pin "17") (pinfunction "B3_17") (pintype "power_in"))
    )
    (net (code "16") (name "/BOOT0") (class "Default")
      (node (ref "R10") (pin "1") (pinfunction "1_1") (pintype "passive"))
      (node (ref "U4") (pin "94") (pinfunction "BOOT0_94") (pintype "power_in"))
    )
    (net (code "17") (name "/BOOT1") (class "Default")
      (node (ref "R7") (pin "2") (pinfunction "2_2") (pintype "passive"))
      (node (ref "U4") (pin "37") (pinfunction "PB2_37") (pintype "power_in"))
    )
    (net (code "18") (name "/Current sens.") (class "Default")
      (node (ref "U4") (pin "26") (pinfunction "PA3_26") (pintype "power_in"))
    )
    (net (code "19") (name "/FMU_AUX1") (class "Default")
      (node (ref "U4") (pin "45") (pinfunction "PE14_45") (pintype "power_in"))
      (node (ref "U9") (pin "6") (pinfunction "A5_6") (pintype "power_in"))
    )
    (net (code "20") (name "/FMU_AUX2") (class "Default")
      (node (ref "U4") (pin "44") (pinfunction "PE13_44") (pintype "power_in"))
      (node (ref "U9") (pin "7") (pinfunction "A6_7") (pintype "power_in"))
    )
    (net (code "21") (name "/FMU_AUX3") (class "Default")
      (node (ref "U4") (pin "42") (pinfunction "PE11_42") (pintype "power_in"))
      (node (ref "U9") (pin "8") (pinfunction "A7_8") (pintype "power_in"))
    )
    (net (code "22") (name "/FMU_AUX4") (class "Default")
      (node (ref "U4") (pin "40") (pinfunction "PE9_40") (pintype "power_in"))
      (node (ref "U9") (pin "9") (pinfunction "A8_9") (pintype "power_in"))
    )
    (net (code "23") (name "/FMU_AUX5") (class "Default")
      (node (ref "U4") (pin "60") (pinfunction "PD13_60") (pintype "power_in"))
      (node (ref "U9") (pin "5") (pinfunction "A4_5") (pintype "power_in"))
    )
    (net (code "24") (name "/FMU_AUX6") (class "Default")
      (node (ref "U4") (pin "61") (pinfunction "PD14_61") (pintype "power_in"))
      (node (ref "U9") (pin "4") (pinfunction "A3_4") (pintype "power_in"))
    )
    (net (code "25") (name "/FMU_RC input") (class "Default")
      (node (ref "U4") (pin "64") (pinfunction "PC7_64") (pintype "power_in"))
      (node (ref "U8") (pin "7") (pinfunction "1Y_7") (pintype "power_in"))
    )
    (net (code "26") (name "/FRAM_SPI_CS") (class "Default")
      (node (ref "U2") (pin "1") (pinfunction "CS_1") (pintype "power_in"))
      (node (ref "U4") (pin "57") (pinfunction "PD10_57") (pintype "power_in"))
    )
    (net (code "27") (name "/FRAM_SPI_MISO") (class "Default")
      (node (ref "U2") (pin "2") (pinfunction "SO_2") (pintype "power_in"))
      (node (ref "U4") (pin "53") (pinfunction "PB14_53") (pintype "power_in"))
      (node (ref "U5") (pin "6") (pinfunction "SDO_6") (pintype "power_in"))
    )
    (net (code "28") (name "/FRAM_SPI_MOSI") (class "Default")
      (node (ref "U2") (pin "5") (pinfunction "SI_5") (pintype "power_in"))
      (node (ref "U4") (pin "54") (pinfunction "PB15_54") (pintype "power_in"))
      (node (ref "U5") (pin "7") (pinfunction "SDI_/__SDA_7") (pintype "power_in"))
    )
    (net (code "29") (name "/FRAM_SPI_SCK") (class "Default")
      (node (ref "U2") (pin "6") (pinfunction "SCK_6") (pintype "power_in"))
      (node (ref "U4") (pin "47") (pinfunction "PB10_47") (pintype "power_in"))
      (node (ref "U5") (pin "8") (pinfunction "SCLK_8") (pintype "power_in"))
    )
    (net (code "30") (name "/GPS_UART_RX") (class "Default")
      (node (ref "U4") (pin "24") (pinfunction "PA1_24") (pintype "power_in"))
    )
    (net (code "31") (name "/GPS_UART_TX") (class "Default")
      (node (ref "U4") (pin "23") (pinfunction "PA0_23") (pintype "power_in"))
    )
    (net (code "32") (name "/I2C_SCL") (class "Default")
      (node (ref "R3") (pin "2") (pinfunction "2_2") (pintype "passive"))
      (node (ref "U4") (pin "95") (pinfunction "PB8_95") (pintype "power_in"))
    )
    (net (code "33") (name "/I2C_SDA") (class "Default")
      (node (ref "R2") (pin "2") (pinfunction "2_2") (pintype "passive"))
      (node (ref "U4") (pin "96") (pinfunction "PB9_96") (pintype "power_in"))
    )
    (net (code "34") (name "/LED_BLUE") (class "Default")
      (node (ref "LED2") (pin "4") (pinfunction "Blue_4") (pintype "power_in"))
      (node (ref "R12") (pin "1") (pinfunction "1_1") (pintype "passive"))
      (node (ref "R12") (pin "2") (pinfunction "2_2") (pintype "passive"))
      (node (ref "U4") (pin "89") (pinfunction "PB3_89") (pintype "power_in"))
    )
    (net (code "35") (name "/LED_GREEN") (class "Default")
      (node (ref "LED2") (pin "2") (pinfunction "Green_2") (pintype "power_in"))
      (node (ref "R13") (pin "1") (pinfunction "1_1") (pintype "passive"))
      (node (ref "R13") (pin "2") (pinfunction "2_2") (pintype "passive"))
      (node (ref "U4") (pin "36") (pinfunction "PB1_36") (pintype "power_in"))
    )
    (net (code "36") (name "/LED_RED") (class "Default")
      (node (ref "LED2") (pin "1") (pinfunction "Red_1") (pintype "power_in"))
      (node (ref "R15") (pin "1") (pinfunction "1_1") (pintype "passive"))
      (node (ref "R15") (pin "2") (pinfunction "2_2") (pintype "passive"))
      (node (ref "U4") (pin "48") (pinfunction "PB11_48") (pintype "power_in"))
    )
    (net (code "37") (name "/MPU9250_SPI_CS") (class "Default")
      (node (ref "U4") (pin "17") (pinfunction "PC2_17") (pintype "power_in"))
      (node (ref "U6") (pin "22") (pinfunction "nCS_22") (pintype "power_in"))
    )
    (net (code "38") (name "/MPU9250_SPI_INT") (class "Default")
      (node (ref "U4") (pin "62") (pinfunction "PD15_62") (pintype "power_in"))
      (node (ref "U6") (pin "12") (pinfunction "INT_12") (pintype "power_in"))
    )
    (net (code "39") (name "/MPU9250_SPI_SCLK") (class "Default")
      (node (ref "U4") (pin "30") (pinfunction "PA5_30") (pintype "power_in"))
      (node (ref "U6") (pin "23") (pinfunction "SCL_/_SCLK_23") (pintype "power_in"))
    )
    (net (code "40") (name "/MPU9250_SPI_SDI") (class "Default")
      (node (ref "U4") (pin "32") (pinfunction "PA7_32") (pintype "power_in"))
      (node (ref "U6") (pin "24") (pinfunction "SDA_/_SDI_24") (pintype "power_in"))
    )
    (net (code "41") (name "/MPU9250_SPI_SDO") (class "Default")
      (node (ref "U4") (pin "31") (pinfunction "PA6_31") (pintype "power_in"))
      (node (ref "U6") (pin "9") (pinfunction "AD0_/_SDO_9") (pintype "power_in"))
    )
    (net (code "42") (name "/MS5607_SPI_ CS") (class "Default")
      (node (ref "U4") (pin "88") (pinfunction "PD7_88") (pintype "power_in"))
      (node (ref "U5") (pin "5") (pinfunction "CSB_5") (pintype "power_in"))
    )
    (net (code "43") (name "/MicroSD_CLK") (class "Default")
      (node (ref "U10") (pin "5") (pinfunction "CLK_5") (pintype "power_in"))
      (node (ref "U4") (pin "80") (pinfunction "PC12_80") (pintype "power_in"))
    )
    (net (code "44") (name "/MicroSD_CMD") (class "Default")
      (node (ref "R16") (pin "2") (pinfunction "2_2") (pintype "passive"))
      (node (ref "U10") (pin "3") (pinfunction "CMD_3") (pintype "power_in"))
      (node (ref "U4") (pin "83") (pinfunction "PD2_83") (pintype "power_in"))
    )
    (net (code "45") (name "/MicroSD_DAT0") (class "Default")
      (node (ref "R20") (pin "2") (pinfunction "2_2") (pintype "passive"))
      (node (ref "U10") (pin "7") (pinfunction "DAT0_7") (pintype "power_in"))
      (node (ref "U4") (pin "65") (pinfunction "PC8_65") (pintype "power_in"))
    )
    (net (code "46") (name "/MicroSD_DAT1") (class "Default")
      (node (ref "R19") (pin "2") (pinfunction "2_2") (pintype "passive"))
      (node (ref "U10") (pin "8") (pinfunction "DAT1_8") (pintype "power_in"))
      (node (ref "U4") (pin "66") (pinfunction "PC9_66") (pintype "power_in"))
    )
    (net (code "47") (name "/MicroSD_DAT2") (class "Default")
      (node (ref "R18") (pin "2") (pinfunction "2_2") (pintype "passive"))
      (node (ref "U10") (pin "1") (pinfunction "DAT2_1") (pintype "power_in"))
      (node (ref "U4") (pin "78") (pinfunction "PC10_78") (pintype "power_in"))
    )
    (net (code "48") (name "/MicroSD_DAT3") (class "Default")
      (node (ref "R17") (pin "2") (pinfunction "2_2") (pintype "passive"))
      (node (ref "U10") (pin "2") (pinfunction "CD/DAT3_2") (pintype "power_in"))
      (node (ref "U4") (pin "79") (pinfunction "PC11_79") (pintype "power_in"))
    )
    (net (code "49") (name "/NRST") (class "Default")
      (node (ref "U4") (pin "14") (pinfunction "NRST_14") (pintype "power_in"))
      (node (ref "U7") (pin "2") (pinfunction "Reset_2") (pintype "power_in"))
    )
    (net (code "50") (name "/OSC_IN") (class "Default")
      (node (ref "C15") (pin "2") (pinfunction "2_2") (pintype "passive"))
      (node (ref "U4") (pin "12") (pinfunction "PH0_12") (pintype "power_in"))
      (node (ref "X1") (pin "3") (pintype "power_in"))
    )
    (net (code "51") (name "/OSC_OUT") (class "Default")
      (node (ref "C25") (pin "1") (pinfunction "1_1") (pintype "passive"))
      (node (ref "U4") (pin "13") (pinfunction "PH1_13") (pintype "power_in"))
      (node (ref "X1") (pin "1") (pintype "power_in"))
    )
    (net (code "52") (name "/RC input") (class "Default")
      (node (ref "R14") (pin "2") (pinfunction "2_2") (pintype "passive"))
      (node (ref "U4") (pin "35") (pinfunction "PB0_35") (pintype "power_in"))
      (node (ref "U8") (pin "2") (pinfunction "1B_2") (pintype "power_in"))
    )
    (net (code "53") (name "/REGOUT") (class "Default")
      (node (ref "C26") (pin "2") (pinfunction "2_2") (pintype "passive"))
      (node (ref "U6") (pin "10") (pinfunction "REGOUT_10") (pintype "power_in"))
    )
    (net (code "54") (name "/RSSI_IN") (class "Default")
      (node (ref "U4") (pin "16") (pinfunction "PC1_16") (pintype "power_in"))
    )
    (net (code "55") (name "/SBUS_INV") (class "Default")
      (node (ref "U4") (pin "7") (pinfunction "PC13_7") (pintype "power_in"))
      (node (ref "U8") (pin "1") (pinfunction "1A_1") (pintype "power_in"))
    )
    (net (code "56") (name "/SWCLK") (class "Default")
      (node (ref "U4") (pin "76") (pinfunction "PA14_76") (pintype "power_in"))
    )
    (net (code "57") (name "/SWDIO") (class "Default")
      (node (ref "U4") (pin "72") (pinfunction "PA13_72") (pintype "power_in"))
    )
    (net (code "58") (name "/Sens. enable") (class "Default")
      (node (ref "U3") (pin "3") (pinfunction "EN_3") (pintype "power_in"))
      (node (ref "U4") (pin "2") (pinfunction "PE3_2") (pintype "power_in"))
    )
    (net (code "59") (name "/Telem1_UART_RX") (class "Default")
      (node (ref "U4") (pin "87") (pinfunction "PD6_87") (pintype "power_in"))
    )
    (net (code "60") (name "/Telem1_UART_TX") (class "Default")
      (node (ref "U4") (pin "86") (pinfunction "PD5_86") (pintype "power_in"))
    )
    (net (code "61") (name "/Telem2_UART_FMU_RX") (class "Default")
      (node (ref "U4") (pin "56") (pinfunction "PD9_56") (pintype "power_in"))
      (node (ref "U9") (pin "3") (pinfunction "A2_3") (pintype "power_in"))
    )
    (net (code "62") (name "/Telem2_UART_FMU_TX") (class "Default")
      (node (ref "U4") (pin "55") (pinfunction "PD8_55") (pintype "power_in"))
      (node (ref "U9") (pin "1") (pinfunction "A1_1") (pintype "power_in"))
    )
    (net (code "63") (name "/Telem2_UART_RX") (class "Default")
      (node (ref "U9") (pin "18") (pinfunction "B2_18") (pintype "power_in"))
    )
    (net (code "64") (name "/Telem2_UART_TX") (class "Default")
      (node (ref "U9") (pin "20") (pinfunction "B1_20") (pintype "power_in"))
    )
    (net (code "65") (name "/USB_D_N") (class "Default")
      (node (ref "U4") (pin "70") (pinfunction "PA11_70") (pintype "power_in"))
    )
    (net (code "66") (name "/USB_D_P") (class "Default")
      (node (ref "U4") (pin "71") (pinfunction "PA12_71") (pintype "power_in"))
    )
    (net (code "67") (name "/VCAP_1") (class "Default")
      (node (ref "C32") (pin "1") (pinfunction "1_1") (pintype "passive"))
      (node (ref "U4") (pin "49") (pinfunction "VCAP_1_49") (pintype "power_in"))
    )
    (net (code "68") (name "/VCAP_2") (class "Default")
      (node (ref "C33") (pin "1") (pinfunction "1_1") (pintype "passive"))
      (node (ref "U4") (pin "73") (pinfunction "VCAP_2_73") (pintype "power_in"))
    )
    (net (code "69") (name "/Voltage sens.") (class "Default")
      (node (ref "U4") (pin "25") (pinfunction "PA2_25") (pintype "power_in"))
    )
    (net (code "70") (name "AGND2") (class "Default")
      (node (ref "C14") (pin "2") (pinfunction "2_2") (pintype "passive"))
      (node (ref "C26") (pin "1") (pinfunction "1_1") (pintype "passive"))
      (node (ref "C27") (pin "1") (pinfunction "1_1") (pintype "passive"))
      (node (ref "C28") (pin "1") (pinfunction "1_1") (pintype "passive"))
      (node (ref "C30") (pin "1") (pinfunction "1_1") (pintype "passive"))
      (node (ref "L11") (pin "1") (pintype "power_in"))
      (node (ref "L14") (pin "1") (pintype "power_in"))
      (node (ref "L7") (pin "1") (pintype "power_in"))
      (node (ref "U4") (pin "20") (pinfunction "VSSA_20") (pintype "power_in"))
      (node (ref "U5") (pin "2") (pinfunction "PS_2") (pintype "power_in"))
      (node (ref "U5") (pin "3") (pinfunction "GND_3") (pintype "power_in"))
      (node (ref "U6") (pin "11") (pinfunction "FSYNC_11") (pintype "power_in"))
      (node (ref "U6") (pin "18") (pinfunction "GND_18") (pintype "power_in"))
      (node (ref "U6") (pin "20") (pinfunction "RESV_20") (pintype "power_in"))
    )
    (net (code "71") (name "GND") (class "Default")
      (node (ref "C1") (pin "1") (pinfunction "1_1") (pintype "passive"))
      (node (ref "C10") (pin "1") (pinfunction "1_1") (pintype "passive"))
      (node (ref "C11") (pin "1") (pinfunction "1_1") (pintype "passive"))
      (node (ref "C12") (pin "1") (pinfunction "1_1") (pintype "passive"))
      (node (ref "C13") (pin "1") (pinfunction "1_1") (pintype "passive"))
      (node (ref "C15") (pin "1") (pinfunction "1_1") (pintype "passive"))
      (node (ref "C16") (pin "2") (pinfunction "2_2") (pintype "passive"))
      (node (ref "C17") (pin "2") (pinfunction "2_2") (pintype "passive"))
      (node (ref "C18") (pin "2") (pinfunction "2_2") (pintype "passive"))
      (node (ref "C19") (pin "2") (pinfunction "2_2") (pintype "passive"))
      (node (ref "C2") (pin "2") (pinfunction "2_2") (pintype "passive"))
      (node (ref "C20") (pin "2") (pinfunction "2_2") (pintype "passive"))
      (node (ref "C21") (pin "2") (pinfunction "2_2") (pintype "passive"))
      (node (ref "C22") (pin "1") (pinfunction "1_1") (pintype "passive"))
      (node (ref "C23") (pin "1") (pinfunction "1_1") (pintype "passive"))
      (node (ref "C24") (pin "1") (pinfunction "1_1") (pintype "passive"))
      (node (ref "C25") (pin "2") (pinfunction "2_2") (pintype "passive"))
      (node (ref "C29") (pin "1") (pinfunction "1_1") (pintype "passive"))
      (node (ref "C3") (pin "2") (pinfunction "2_2") (pintype "passive"))
      (node (ref "C31") (pin "2") (pinfunction "2_2") (pintype "passive"))
      (node (ref "C32") (pin "2") (pinfunction "2_2") (pintype "passive"))
      (node (ref "C33") (pin "2") (pinfunction "2_2") (pintype "passive"))
      (node (ref "C34") (pin "1") (pinfunction "1_1") (pintype "passive"))
      (node (ref "C35") (pin "1") (pinfunction "1_1") (pintype "passive"))
      (node (ref "C36") (pin "2") (pinfunction "2_2") (pintype "passive"))
      (node (ref "C37") (pin "2") (pinfunction "2_2") (pintype "passive"))
      (node (ref "C4") (pin "2") (pinfunction "2_2") (pintype "passive"))
      (node (ref "C5") (pin "2") (pinfunction "2_2") (pintype "passive"))
      (node (ref "C6") (pin "2") (pinfunction "2_2") (pintype "passive"))
      (node (ref "C7") (pin "2") (pinfunction "2_2") (pintype "passive"))
      (node (ref "C8") (pin "1") (pinfunction "1_1") (pintype "passive"))
      (node (ref "C9") (pin "1") (pinfunction "1_1") (pintype "passive"))
      (node (ref "L11") (pin "2") (pintype "power_in"))
      (node (ref "L14") (pin "2") (pintype "power_in"))
      (node (ref "L7") (pin "2") (pintype "power_in"))
      (node (ref "R1") (pin "2") (pinfunction "2_2") (pintype "passive"))
      (node (ref "R10") (pin "2") (pinfunction "2_2") (pintype "passive"))
      (node (ref "R11") (pin "1") (pinfunction "1_1") (pintype "passive"))
      (node (ref "R14") (pin "1") (pinfunction "1_1") (pintype "passive"))
      (node (ref "R5") (pin "2") (pinfunction "2_2") (pintype "passive"))
      (node (ref "R6") (pin "2") (pinfunction "2_2") (pintype "passive"))
      (node (ref "R7") (pin "1") (pinfunction "1_1") (pintype "passive"))
      (node (ref "R9") (pin "2") (pinfunction "2_2") (pintype "passive"))
      (node (ref "U1") (pin "2") (pinfunction "GND_2") (pintype "power_in"))
      (node (ref "U1") (pin "4") (pinfunction "NC_4") (pintype "open_collector"))
      (node (ref "U10") (pin "11") (pinfunction "GND_11") (pintype "power_in"))
      (node (ref "U10") (pin "6") (pinfunction "VSS_6") (pintype "power_in"))
      (node (ref "U2") (pin "4") (pinfunction "VSS_4") (pintype "power_in"))
      (node (ref "U3") (pin "2") (pinfunction "GND_2") (pintype "power_in"))
      (node (ref "U3") (pin "4") (pinfunction "NC_4") (pintype "open_collector"))
      (node (ref "U4") (pin "10") (pinfunction "VSS_10") (pintype "power_in"))
      (node (ref "U4") (pin "27") (pinfunction "VSS_27") (pintype "power_in"))
      (node (ref "U4") (pin "74") (pinfunction "VSS_74") (pintype "power_in"))
      (node (ref "U4") (pin "99") (pinfunction "VSS_99") (pintype "power_in"))
      (node (ref "U7") (pin "1") (pinfunction "GND_1") (pintype "power_in"))
      (node (ref "U8") (pin "4") (pinfunction "GND_4") (pintype "power_in"))
      (node (ref "U8") (pin "5") (pinfunction "2A_5") (pintype "power_in"))
      (node (ref "U8") (pin "6") (pinfunction "2B_6") (pintype "power_in"))
      (node (ref "U9") (pin "11") (pinfunction "GND_11") (pintype "power_in"))
      (node (ref "U9") (pin "21") (pinfunction "Exposed_pad_21") (pintype "power_in"))
      (node (ref "X1") (pin "2") (pinfunction "GND_2") (pintype "power_in"))
      (node (ref "X1") (pin "4") (pinfunction "GND_4") (pintype "power_in"))
    )
    (net (code "72") (name "unconnected-(U4-PA8-Pad67)") (class "Default")
      (node (ref "U4") (pin "67") (pinfunction "PA8_67") (pintype "power_in"))
    )
    (net (code "73") (name "unconnected-(U4-PA10-Pad69)") (class "Default")
      (node (ref "U4") (pin "69") (pinfunction "PA10_69") (pintype "power_in"))
    )
    (net (code "74") (name "unconnected-(U4-PA15-Pad77)") (class "Default")
      (node (ref "U4") (pin "77") (pinfunction "PA15_77") (pintype "power_in"))
    )
    (net (code "75") (name "unconnected-(U4-PB4-Pad90)") (class "Default")
      (node (ref "U4") (pin "90") (pinfunction "PB4_90") (pintype "power_in"))
    )
    (net (code "76") (name "unconnected-(U4-PB6-Pad92)") (class "Default")
      (node (ref "U4") (pin "92") (pinfunction "PB6_92") (pintype "power_in"))
    )
    (net (code "77") (name "unconnected-(U4-PB7-Pad93)") (class "Default")
      (node (ref "U4") (pin "93") (pinfunction "PB7_93") (pintype "power_in"))
    )
    (net (code "78") (name "unconnected-(U4-PB12-Pad51)") (class "Default")
      (node (ref "U4") (pin "51") (pinfunction "PB12_51") (pintype "power_in"))
    )
    (net (code "79") (name "unconnected-(U4-PB13-Pad52)") (class "Default")
      (node (ref "U4") (pin "52") (pinfunction "PB13_52") (pintype "power_in"))
    )
    (net (code "80") (name "unconnected-(U4-PC3-Pad18)") (class "Default")
      (node (ref "U4") (pin "18") (pinfunction "PC3_18") (pintype "power_in"))
    )
    (net (code "81") (name "unconnected-(U4-PC4-Pad33)") (class "Default")
      (node (ref "U4") (pin "33") (pinfunction "PC4_33") (pintype "power_in"))
    )
    (net (code "82") (name "unconnected-(U4-PC5-Pad34)") (class "Default")
      (node (ref "U4") (pin "34") (pinfunction "PC5_34") (pintype "power_in"))
    )
    (net (code "83") (name "unconnected-(U4-PC6-Pad63)") (class "Default")
      (node (ref "U4") (pin "63") (pinfunction "PC6_63") (pintype "power_in"))
    )
    (net (code "84") (name "unconnected-(U4-PC14-Pad8)") (class "Default")
      (node (ref "U4") (pin "8") (pinfunction "PC14_8") (pintype "power_in"))
    )
    (net (code "85") (name "unconnected-(U4-PC15-Pad9)") (class "Default")
      (node (ref "U4") (pin "9") (pinfunction "PC15_9") (pintype "power_in"))
    )
    (net (code "86") (name "unconnected-(U4-PD0-Pad81)") (class "Default")
      (node (ref "U4") (pin "81") (pinfunction "PD0_81") (pintype "power_in"))
    )
    (net (code "87") (name "unconnected-(U4-PD1-Pad82)") (class "Default")
      (node (ref "U4") (pin "82") (pinfunction "PD1_82") (pintype "power_in"))
    )
    (net (code "88") (name "unconnected-(U4-PD3-Pad84)") (class "Default")
      (node (ref "U4") (pin "84") (pinfunction "PD3_84") (pintype "power_in"))
    )
    (net (code "89") (name "unconnected-(U4-PD4-Pad85)") (class "Default")
      (node (ref "U4") (pin "85") (pinfunction "PD4_85") (pintype "power_in"))
    )
    (net (code "90") (name "unconnected-(U4-PD11-Pad58)") (class "Default")
      (node (ref "U4") (pin "58") (pinfunction "PD11_58") (pintype "power_in"))
    )
    (net (code "91") (name "unconnected-(U4-PD12-Pad59)") (class "Default")
      (node (ref "U4") (pin "59") (pinfunction "PD12_59") (pintype "power_in"))
    )
    (net (code "92") (name "unconnected-(U4-PE0-Pad97)") (class "Default")
      (node (ref "U4") (pin "97") (pinfunction "PE0_97") (pintype "power_in"))
    )
    (net (code "93") (name "unconnected-(U4-PE1-Pad98)") (class "Default")
      (node (ref "U4") (pin "98") (pinfunction "PE1_98") (pintype "power_in"))
    )
    (net (code "94") (name "unconnected-(U4-PE2-Pad1)") (class "Default")
      (node (ref "U4") (pin "1") (pinfunction "PE2_1") (pintype "power_in"))
    )
    (net (code "95") (name "unconnected-(U4-PE4-Pad3)") (class "Default")
      (node (ref "U4") (pin "3") (pinfunction "PE4_3") (pintype "power_in"))
    )
    (net (code "96") (name "unconnected-(U4-PE5-Pad4)") (class "Default")
      (node (ref "U4") (pin "4") (pinfunction "PE5_4") (pintype "power_in"))
    )
    (net (code "97") (name "unconnected-(U4-PE6-Pad5)") (class "Default")
      (node (ref "U4") (pin "5") (pinfunction "PE6_5") (pintype "power_in"))
    )
    (net (code "98") (name "unconnected-(U4-PE7-Pad38)") (class "Default")
      (node (ref "U4") (pin "38") (pinfunction "PE7_38") (pintype "power_in"))
    )
    (net (code "99") (name "unconnected-(U4-PE8-Pad39)") (class "Default")
      (node (ref "U4") (pin "39") (pinfunction "PE8_39") (pintype "power_in"))
    )
    (net (code "100") (name "unconnected-(U4-PE10-Pad41)") (class "Default")
      (node (ref "U4") (pin "41") (pinfunction "PE10_41") (pintype "power_in"))
    )
    (net (code "101") (name "unconnected-(U4-PE12-Pad43)") (class "Default")
      (node (ref "U4") (pin "43") (pinfunction "PE12_43") (pintype "power_in"))
    )
    (net (code "102") (name "unconnected-(U4-PE15-Pad46)") (class "Default")
      (node (ref "U4") (pin "46") (pinfunction "PE15_46") (pintype "power_in"))
    )
    (net (code "103") (name "unconnected-(U5-CSB-Pad4)") (class "Default")
      (node (ref "U5") (pin "4") (pinfunction "CSB_4") (pintype "power_in"))
    )
    (net (code "104") (name "unconnected-(U6-AUX_CL-Pad7)") (class "Default")
      (node (ref "U6") (pin "7") (pinfunction "AUX_CL_7") (pintype "power_in"))
    )
    (net (code "105") (name "unconnected-(U6-AUX_DA-Pad21)") (class "Default")
      (node (ref "U6") (pin "21") (pinfunction "AUX_DA_21") (pintype "power_in"))
    )
    (net (code "106") (name "unconnected-(U6-NC-Pad2)") (class "Default")
      (node (ref "U6") (pin "2") (pinfunction "NC_2") (pintype "power_in"))
    )
    (net (code "107") (name "unconnected-(U6-NC-Pad3)") (class "Default")
      (node (ref "U6") (pin "3") (pinfunction "NC_3") (pintype "power_in"))
    )
    (net (code "108") (name "unconnected-(U6-NC-Pad4)") (class "Default")
      (node (ref "U6") (pin "4") (pinfunction "NC_4") (pintype "power_in"))
    )
    (net (code "109") (name "unconnected-(U6-NC-Pad5)") (class "Default")
      (node (ref "U6") (pin "5") (pinfunction "NC_5") (pintype "power_in"))
    )
    (net (code "110") (name "unconnected-(U6-NC-Pad6)") (class "Default")
      (node (ref "U6") (pin "6") (pinfunction "NC_6") (pintype "power_in"))
    )
    (net (code "111") (name "unconnected-(U6-NC-Pad14)") (class "Default")
      (node (ref "U6") (pin "14") (pinfunction "NC_14") (pintype "power_in"))
    )
    (net (code "112") (name "unconnected-(U6-NC-Pad15)") (class "Default")
      (node (ref "U6") (pin "15") (pinfunction "NC_15") (pintype "power_in"))
    )
    (net (code "113") (name "unconnected-(U6-NC-Pad16)") (class "Default")
      (node (ref "U6") (pin "16") (pinfunction "NC_16") (pintype "power_in"))
    )
    (net (code "114") (name "unconnected-(U6-NC-Pad17)") (class "Default")
      (node (ref "U6") (pin "17") (pinfunction "NC_17") (pintype "power_in"))
    )
    (net (code "115") (name "unconnected-(U6-RESV-Pad19)") (class "Default")
      (node (ref "U6") (pin "19") (pinfunction "RESV_19") (pintype "power_in"))
    )
    (net (code "116") (name "unconnected-(U8-2Y-Pad3)") (class "Default")
      (node (ref "U8") (pin "3") (pinfunction "2Y_3") (pintype "power_in"))
    )
    (net (code "117") (name "unconnected-(U10-SD_DET._SW._1-Pad9)") (class "Default")
      (node (ref "U10") (pin "9") (pinfunction "SD_DET._SW._1_9") (pintype "power_in"))
    )
    (net (code "118") (name "unconnected-(U10-SD_DET._SW._2-Pad10)") (class "Default")
      (node (ref "U10") (pin "10") (pinfunction "SD_DET._SW._2_10") (pintype "power_in"))
    )
  )
)
